# festBin.net
KiCad netlist of a schematic drawn in EAGLE
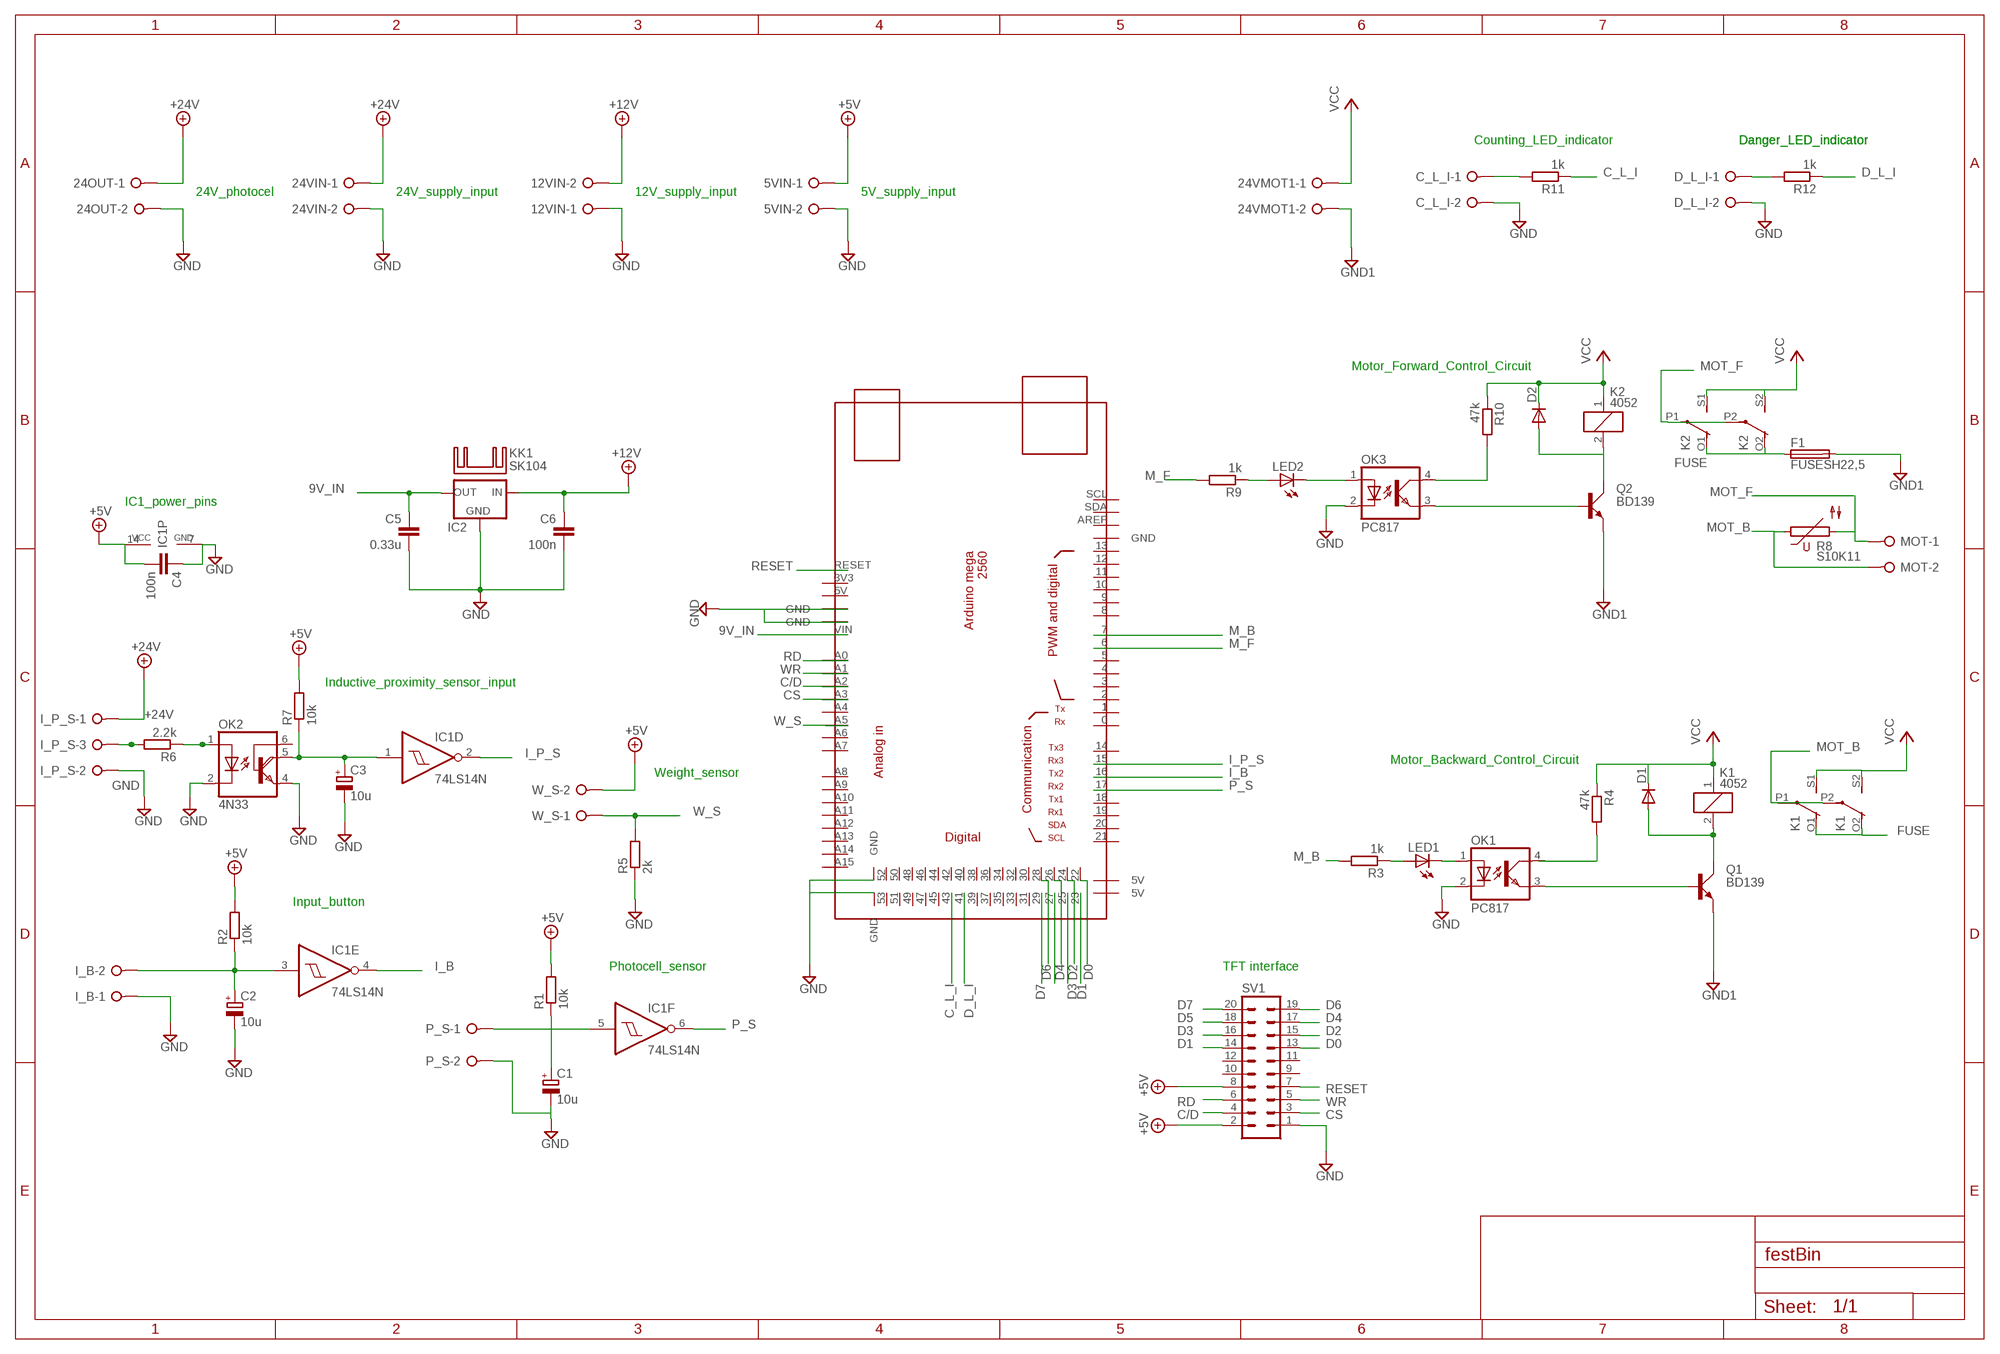
[diagram p0: schematic, sheet 1]

(export (version "E")
  (design (tool "Eeschema 10.0.6"))
  (components
    (comp (ref "5VIN")
      (value "W237-02P")
      (footprint "eagle-import:W237-132")
      (libsource (lib "eagle-import") (part "W237-02P"))
    )
    (comp (ref "12VIN")
      (value "W237-02P")
      (footprint "eagle-import:W237-132")
      (libsource (lib "eagle-import") (part "W237-02P"))
    )
    (comp (ref "24OUT")
      (value "W237-02P")
      (footprint "eagle-import:W237-132")
      (libsource (lib "eagle-import") (part "W237-02P"))
    )
    (comp (ref "24VIN")
      (value "W237-02P")
      (footprint "eagle-import:W237-132")
      (libsource (lib "eagle-import") (part "W237-02P"))
    )
    (comp (ref "24VMOT1")
      (value "W237-02P")
      (footprint "eagle-import:W237-132")
      (libsource (lib "eagle-import") (part "W237-02P"))
    )
    (comp (ref "C1")
      (value "10u")
      (footprint "eagle-import:E2,5-6")
      (libsource (lib "eagle-import") (part "CPOL-EUE2.5-6"))
    )
    (comp (ref "C2")
      (value "10u")
      (footprint "eagle-import:E2,5-6")
      (libsource (lib "eagle-import") (part "CPOL-EUE2.5-6"))
    )
    (comp (ref "C3")
      (value "10u")
      (footprint "eagle-import:E2,5-6")
      (libsource (lib "eagle-import") (part "CPOL-EUE2.5-6"))
    )
    (comp (ref "C4")
      (value "100n")
      (footprint "eagle-import:C050-024X044")
      (libsource (lib "eagle-import") (part "C-EU050-024X044"))
    )
    (comp (ref "C5")
      (value "0.33u")
      (footprint "eagle-import:C050-024X044")
      (libsource (lib "eagle-import") (part "C-EU050-024X044"))
    )
    (comp (ref "C6")
      (value "100n")
      (footprint "eagle-import:C050-024X044")
      (libsource (lib "eagle-import") (part "C-EU050-024X044"))
    )
    (comp (ref "C_L_I")
      (value "W237-02P")
      (footprint "eagle-import:W237-132")
      (libsource (lib "eagle-import") (part "W237-02P"))
    )
    (comp (ref "D1")
      (value "DIODE-DO41-10")
      (footprint "eagle-import:DO41-10")
      (libsource (lib "eagle-import") (part "DIODE-DO41-10"))
    )
    (comp (ref "D2")
      (value "DIODE-DO41-10")
      (footprint "eagle-import:DO41-10")
      (libsource (lib "eagle-import") (part "DIODE-DO41-10"))
    )
    (comp (ref "D_L_I")
      (value "W237-02P")
      (footprint "eagle-import:W237-132")
      (fields (field (name "OC_FARNELL") "unknown") (field (name "OC_NEWARK") "unknown"))
      (libsource (lib "eagle-import") (part "W237-02P"))
    )
    (comp (ref "F1")
      (value "FUSESH22,5")
      (footprint "eagle-import:SH22,5")
      (libsource (lib "eagle-import") (part "FUSESH22,5"))
    )
    (comp (ref "IC1")
      (value "74LS14N")
      (footprint "eagle-import:DIL14")
      (libsource (lib "eagle-import") (part "7414NLS"))
    )
    (comp (ref "IC2")
      (value "78XXS")
      (footprint "eagle-import:78XXS")
      (libsource (lib "eagle-import") (part "78XXS"))
    )
    (comp (ref "I_B")
      (value "W237-02P")
      (footprint "eagle-import:W237-132")
      (libsource (lib "eagle-import") (part "W237-02P"))
    )
    (comp (ref "I_P_S")
      (value "W237-3E")
      (footprint "eagle-import:W237-3E")
      (libsource (lib "eagle-import") (part "W237-3E"))
    )
    (comp (ref "K1")
      (value "4052")
      (footprint "eagle-import:F4052")
      (libsource (lib "eagle-import") (part "4052"))
    )
    (comp (ref "K2")
      (value "4052")
      (footprint "eagle-import:F4052")
      (libsource (lib "eagle-import") (part "4052"))
    )
    (comp (ref "KK1")
      (value "SK104")
      (footprint "eagle-import:SK104")
      (libsource (lib "eagle-import") (part "SK104"))
    )
    (comp (ref "LED1")
      (value "LED3MM")
      (footprint "eagle-import:LED3MM")
      (libsource (lib "eagle-import") (part "LED3MM"))
    )
    (comp (ref "LED2")
      (value "LED3MM")
      (footprint "eagle-import:LED3MM")
      (libsource (lib "eagle-import") (part "LED3MM"))
    )
    (comp (ref "MOT")
      (value "W237-02P")
      (footprint "eagle-import:W237-132")
      (fields (field (name "OC_FARNELL") "unknown") (field (name "OC_NEWARK") "unknown"))
      (libsource (lib "eagle-import") (part "W237-02P"))
    )
    (comp (ref "OK1")
      (value "PC817")
      (footprint "eagle-import:DIL04")
      (fields (field (name "MPN") "PC817X4J000F"))
      (libsource (lib "eagle-import") (part "PC817"))
    )
    (comp (ref "OK2")
      (value "4N33")
      (footprint "eagle-import:DIL06")
      (fields (field (name "MF") "VISHAY/TELEFUNKEN"))
      (libsource (lib "eagle-import") (part "4N33"))
    )
    (comp (ref "OK3")
      (value "PC817")
      (footprint "eagle-import:DIL04")
      (fields (field (name "MPN") "PC817X4J000F"))
      (libsource (lib "eagle-import") (part "PC817"))
    )
    (comp (ref "P_S")
      (value "W237-02P")
      (footprint "eagle-import:W237-132")
      (libsource (lib "eagle-import") (part "W237-02P"))
    )
    (comp (ref "Q1")
      (value "BD139")
      (footprint "eagle-import:TO126AV")
      (libsource (lib "eagle-import") (part "BD139"))
    )
    (comp (ref "Q2")
      (value "BD139")
      (footprint "eagle-import:TO126AV")
      (libsource (lib "eagle-import") (part "BD139"))
    )
    (comp (ref "R1")
      (value "10k")
      (footprint "eagle-import:0207_10")
      (libsource (lib "eagle-import") (part "R-EU_0207/10"))
    )
    (comp (ref "R2")
      (value "10k")
      (footprint "eagle-import:0207_10")
      (libsource (lib "eagle-import") (part "R-EU_0207/10"))
    )
    (comp (ref "R3")
      (value "1k")
      (footprint "eagle-import:0207_10")
      (libsource (lib "eagle-import") (part "R-EU_0207/10"))
    )
    (comp (ref "R4")
      (value "47k")
      (footprint "eagle-import:0207_10")
      (libsource (lib "eagle-import") (part "R-EU_0207/10"))
    )
    (comp (ref "R5")
      (value "2k")
      (footprint "eagle-import:0207_10")
      (libsource (lib "eagle-import") (part "R-EU_0207/10"))
    )
    (comp (ref "R6")
      (value "2.2k")
      (footprint "eagle-import:0207_10")
      (libsource (lib "eagle-import") (part "R-EU_0207/10"))
    )
    (comp (ref "R7")
      (value "10k")
      (footprint "eagle-import:0207_10")
      (libsource (lib "eagle-import") (part "R-EU_0207/10"))
    )
    (comp (ref "R8")
      (value "S10K11")
      (footprint "eagle-import:S10K11")
      (libsource (lib "eagle-import") (part "S10K11"))
    )
    (comp (ref "R9")
      (value "1k")
      (footprint "eagle-import:0207_10")
      (libsource (lib "eagle-import") (part "R-EU_0207/10"))
    )
    (comp (ref "R10")
      (value "47k")
      (footprint "eagle-import:0207_10")
      (libsource (lib "eagle-import") (part "R-EU_0207/10"))
    )
    (comp (ref "R11")
      (value "1k")
      (footprint "eagle-import:0207_10")
      (libsource (lib "eagle-import") (part "R-EU_0207/10"))
    )
    (comp (ref "R12")
      (value "1k")
      (footprint "eagle-import:0207_10")
      (libsource (lib "eagle-import") (part "R-EU_0207/10"))
    )
    (comp (ref "SV1")
      (value "ML20")
      (footprint "eagle-import:ML20")
      (libsource (lib "eagle-import") (part "ML20"))
    )
    (comp (ref "U$1")
      (value "MEGA_DEVICE")
      (footprint "eagle-import:MEGABOX")
      (libsource (lib "eagle-import") (part "MEGA_DEVICE"))
    )
    (comp (ref "W_S")
      (value "W237-02P")
      (footprint "eagle-import:W237-132")
      (libsource (lib "eagle-import") (part "W237-02P"))
    )
  )
  (nets
    (net (code "1") (name "+5V") (class "Default")
      (node (ref "5VIN") (pin "1") (pinfunction "KL_1") (pintype "passive"))
      (node (ref "C4") (pin "2") (pinfunction "2_2") (pintype "passive"))
      (node (ref "IC1") (pin "14") (pinfunction "VCC_14") (pintype "power_in"))
      (node (ref "R1") (pin "2") (pinfunction "2_2") (pintype "passive"))
      (node (ref "R2") (pin "2") (pinfunction "2_2") (pintype "passive"))
      (node (ref "R7") (pin "2") (pinfunction "2_2") (pintype "passive"))
      (node (ref "SV1") (pin "2") (pinfunction "2_2") (pintype "passive"))
      (node (ref "SV1") (pin "8") (pinfunction "8_8") (pintype "passive"))
      (node (ref "W_S") (pin "2") (pinfunction "KL_2") (pintype "passive"))
    )
    (net (code "2") (name "+12V") (class "Default")
      (node (ref "12VIN") (pin "2") (pinfunction "KL_2") (pintype "passive"))
      (node (ref "C6") (pin "1") (pinfunction "1_1") (pintype "passive"))
      (node (ref "IC2") (pin "IN") (pinfunction "IN_IN") (pintype "input"))
    )
    (net (code "3") (name "+24V") (class "Default")
      (node (ref "24OUT") (pin "1") (pinfunction "KL_1") (pintype "passive"))
      (node (ref "24VIN") (pin "1") (pinfunction "KL_1") (pintype "passive"))
      (node (ref "I_P_S") (pin "1") (pinfunction "KL_1") (pintype "passive"))
    )
    (net (code "4") (name "/9V_IN") (class "Default")
      (node (ref "C5") (pin "1") (pinfunction "1_1") (pintype "passive"))
      (node (ref "IC2") (pin "OUT") (pinfunction "OUT_OUT") (pintype "passive"))
      (node (ref "U$1") (pin "VIN") (pinfunction "VIN_VIN") (pintype "bidirectional"))
    )
    (net (code "5") (name "/CS") (class "Default")
      (node (ref "SV1") (pin "3") (pinfunction "3_3") (pintype "passive"))
      (node (ref "U$1") (pin "A3") (pinfunction "A3_A3") (pintype "bidirectional"))
    )
    (net (code "6") (name "/C_L_I") (class "Default")
      (node (ref "R11") (pin "1") (pinfunction "1_1") (pintype "passive"))
      (node (ref "U$1") (pin "43") (pinfunction "43_43") (pintype "bidirectional"))
    )
    (net (code "7") (name "/C{slash}D") (class "Default")
      (node (ref "SV1") (pin "4") (pinfunction "4_4") (pintype "passive"))
      (node (ref "U$1") (pin "A2") (pinfunction "A2_A2") (pintype "bidirectional"))
    )
    (net (code "8") (name "/D0") (class "Default")
      (node (ref "SV1") (pin "13") (pinfunction "13_13") (pintype "passive"))
      (node (ref "U$1") (pin "22") (pinfunction "22_22") (pintype "bidirectional"))
    )
    (net (code "9") (name "/D1") (class "Default")
      (node (ref "SV1") (pin "14") (pinfunction "14_14") (pintype "passive"))
      (node (ref "U$1") (pin "23") (pinfunction "23_23") (pintype "bidirectional"))
    )
    (net (code "10") (name "/D2") (class "Default")
      (node (ref "SV1") (pin "15") (pinfunction "15_15") (pintype "passive"))
      (node (ref "U$1") (pin "24") (pinfunction "24_24") (pintype "bidirectional"))
    )
    (net (code "11") (name "/D3") (class "Default")
      (node (ref "SV1") (pin "16") (pinfunction "16_16") (pintype "passive"))
      (node (ref "U$1") (pin "25") (pinfunction "25_25") (pintype "bidirectional"))
    )
    (net (code "12") (name "/D4") (class "Default")
      (node (ref "SV1") (pin "17") (pinfunction "17_17") (pintype "passive"))
      (node (ref "U$1") (pin "26") (pinfunction "26_26") (pintype "bidirectional"))
    )
    (net (code "13") (name "/D5") (class "Default")
      (node (ref "SV1") (pin "18") (pinfunction "18_18") (pintype "passive"))
      (node (ref "U$1") (pin "27") (pinfunction "27_27") (pintype "bidirectional"))
    )
    (net (code "14") (name "/D6") (class "Default")
      (node (ref "SV1") (pin "19") (pinfunction "19_19") (pintype "passive"))
      (node (ref "U$1") (pin "28") (pinfunction "28_28") (pintype "bidirectional"))
    )
    (net (code "15") (name "/D7") (class "Default")
      (node (ref "SV1") (pin "20") (pinfunction "20_20") (pintype "passive"))
      (node (ref "U$1") (pin "29") (pinfunction "29_29") (pintype "bidirectional"))
    )
    (net (code "16") (name "/D_L_I") (class "Default")
      (node (ref "R12") (pin "1") (pinfunction "1_1") (pintype "passive"))
      (node (ref "U$1") (pin "41") (pinfunction "41_41") (pintype "bidirectional"))
    )
    (net (code "17") (name "/FUSE") (class "Default")
      (node (ref "F1") (pin "1") (pinfunction "1_1") (pintype "passive"))
      (node (ref "K1") (pin "O1") (pinfunction "O_O1") (pintype "passive"))
      (node (ref "K1") (pin "O2") (pinfunction "O_O2") (pintype "passive"))
      (node (ref "K2") (pin "O1") (pinfunction "O_O1") (pintype "passive"))
      (node (ref "K2") (pin "O2") (pinfunction "O_O2") (pintype "passive"))
    )
    (net (code "18") (name "/I_B") (class "Default")
      (node (ref "IC1") (pin "4") (pinfunction "O_4") (pintype "output"))
      (node (ref "U$1") (pin "16") (pinfunction "16_16") (pintype "bidirectional"))
    )
    (net (code "19") (name "/I_P_S") (class "Default")
      (node (ref "IC1") (pin "2") (pinfunction "O_2") (pintype "output"))
      (node (ref "U$1") (pin "15") (pinfunction "15_15") (pintype "bidirectional"))
    )
    (net (code "20") (name "/MOT_B") (class "Default")
      (node (ref "K1") (pin "P1") (pinfunction "P_P1") (pintype "passive"))
      (node (ref "K1") (pin "P2") (pinfunction "P_P2") (pintype "passive"))
      (node (ref "MOT") (pin "2") (pinfunction "KL_2") (pintype "passive"))
      (node (ref "R8") (pin "1") (pinfunction "1_1") (pintype "passive"))
    )
    (net (code "21") (name "/MOT_F") (class "Default")
      (node (ref "K2") (pin "P1") (pinfunction "P_P1") (pintype "passive"))
      (node (ref "K2") (pin "P2") (pinfunction "P_P2") (pintype "passive"))
      (node (ref "MOT") (pin "1") (pinfunction "KL_1") (pintype "passive"))
      (node (ref "R8") (pin "2") (pinfunction "2_2") (pintype "passive"))
    )
    (net (code "22") (name "/M_B") (class "Default")
      (node (ref "R3") (pin "2") (pinfunction "2_2") (pintype "passive"))
      (node (ref "U$1") (pin "7") (pinfunction "7_7") (pintype "bidirectional"))
    )
    (net (code "23") (name "/M_F") (class "Default")
      (node (ref "R9") (pin "2") (pinfunction "2_2") (pintype "passive"))
      (node (ref "U$1") (pin "6") (pinfunction "6_6") (pintype "bidirectional"))
    )
    (net (code "24") (name "/P_S") (class "Default")
      (node (ref "IC1") (pin "6") (pinfunction "O_6") (pintype "output"))
      (node (ref "U$1") (pin "17") (pinfunction "17_17") (pintype "bidirectional"))
    )
    (net (code "25") (name "/RD") (class "Default")
      (node (ref "SV1") (pin "6") (pinfunction "6_6") (pintype "passive"))
      (node (ref "U$1") (pin "A0") (pinfunction "A0_A0") (pintype "bidirectional"))
    )
    (net (code "26") (name "/RESET") (class "Default")
      (node (ref "SV1") (pin "7") (pinfunction "7_7") (pintype "passive"))
      (node (ref "U$1") (pin "RESET") (pinfunction "RESET_RESET") (pintype "bidirectional"))
    )
    (net (code "27") (name "/WR") (class "Default")
      (node (ref "SV1") (pin "5") (pinfunction "5_5") (pintype "passive"))
      (node (ref "U$1") (pin "A1") (pinfunction "A1_A1") (pintype "bidirectional"))
    )
    (net (code "28") (name "/W_S") (class "Default")
      (node (ref "R5") (pin "2") (pinfunction "2_2") (pintype "passive"))
      (node (ref "U$1") (pin "A5") (pinfunction "A5_A5") (pintype "bidirectional"))
      (node (ref "W_S") (pin "1") (pinfunction "KL_1") (pintype "passive"))
    )
    (net (code "29") (name "GND") (class "Default")
      (node (ref "12VIN") (pin "1") (pinfunction "KL_1") (pintype "passive"))
      (node (ref "24OUT") (pin "2") (pinfunction "KL_2") (pintype "passive"))
      (node (ref "24VIN") (pin "2") (pinfunction "KL_2") (pintype "passive"))
      (node (ref "5VIN") (pin "2") (pinfunction "KL_2") (pintype "passive"))
      (node (ref "C1") (pin "-") (pinfunction "-_-") (pintype "passive"))
      (node (ref "C2") (pin "-") (pinfunction "-_-") (pintype "passive"))
      (node (ref "C3") (pin "-") (pinfunction "-_-") (pintype "passive"))
      (node (ref "C4") (pin "1") (pinfunction "1_1") (pintype "passive"))
      (node (ref "C5") (pin "2") (pinfunction "2_2") (pintype "passive"))
      (node (ref "C6") (pin "2") (pinfunction "2_2") (pintype "passive"))
      (node (ref "C_L_I") (pin "2") (pinfunction "KL_2") (pintype "passive"))
      (node (ref "D_L_I") (pin "2") (pinfunction "KL_2") (pintype "passive"))
      (node (ref "IC1") (pin "7") (pinfunction "GND_7") (pintype "power_in"))
      (node (ref "IC2") (pin "GND") (pinfunction "GND_GND") (pintype "input"))
      (node (ref "I_B") (pin "1") (pinfunction "KL_1") (pintype "passive"))
      (node (ref "I_P_S") (pin "2") (pinfunction "KL_2") (pintype "passive"))
      (node (ref "OK1") (pin "2") (pinfunction "C_2") (pintype "passive"))
      (node (ref "OK2") (pin "2") (pinfunction "C_2") (pintype "passive"))
      (node (ref "OK2") (pin "4") (pinfunction "E_4") (pintype "passive"))
      (node (ref "OK3") (pin "2") (pinfunction "C_2") (pintype "passive"))
      (node (ref "P_S") (pin "2") (pinfunction "KL_2") (pintype "passive"))
      (node (ref "R5") (pin "1") (pinfunction "1_1") (pintype "passive"))
      (node (ref "SV1") (pin "1") (pinfunction "1_1") (pintype "passive"))
      (node (ref "U$1") (pin "GND@2") (pinfunction "GND_GND@2") (pintype "bidirectional"))
      (node (ref "U$1") (pin "GND@3") (pinfunction "GND_GND@3") (pintype "bidirectional"))
      (node (ref "U$1") (pin "GND@6") (pinfunction "GND_GND@6") (pintype "bidirectional"))
      (node (ref "U$1") (pin "GND@7") (pinfunction "GND_GND@7") (pintype "bidirectional"))
    )
    (net (code "30") (name "GND1") (class "Default")
      (node (ref "24VMOT1") (pin "2") (pinfunction "KL_2") (pintype "passive"))
      (node (ref "F1") (pin "2") (pinfunction "2_2") (pintype "passive"))
      (node (ref "Q1") (pin "E") (pinfunction "E_E") (pintype "passive"))
      (node (ref "Q2") (pin "E") (pinfunction "E_E") (pintype "passive"))
    )
    (net (code "31") (name "Net-(C_L_IA-KL)") (class "Default")
      (node (ref "C_L_I") (pin "1") (pinfunction "KL_1") (pintype "passive"))
      (node (ref "R11") (pin "2") (pinfunction "2_2") (pintype "passive"))
    )
    (net (code "32") (name "Net-(D1-PadA)") (class "Default")
      (node (ref "D1") (pin "A") (pinfunction "A_A") (pintype "passive"))
      (node (ref "K1") (pin "2") (pinfunction "2_2") (pintype "passive"))
      (node (ref "Q1") (pin "C") (pinfunction "C_C") (pintype "passive"))
    )
    (net (code "33") (name "Net-(D2-PadA)") (class "Default")
      (node (ref "D2") (pin "A") (pinfunction "A_A") (pintype "passive"))
      (node (ref "K2") (pin "2") (pinfunction "2_2") (pintype "passive"))
      (node (ref "Q2") (pin "C") (pinfunction "C_C") (pintype "passive"))
    )
    (net (code "34") (name "Net-(D_L_IA-KL)") (class "Default")
      (node (ref "D_L_I") (pin "1") (pinfunction "KL_1") (pintype "passive"))
      (node (ref "R12") (pin "2") (pinfunction "2_2") (pintype "passive"))
    )
    (net (code "35") (name "Net-(IC1D-I)") (class "Default")
      (node (ref "C3") (pin "+") (pinfunction "+_+") (pintype "passive"))
      (node (ref "IC1") (pin "1") (pinfunction "I_1") (pintype "input"))
      (node (ref "OK2") (pin "5") (pinfunction "COL_5") (pintype "passive"))
      (node (ref "R7") (pin "1") (pinfunction "1_1") (pintype "passive"))
    )
    (net (code "36") (name "Net-(IC1E-I)") (class "Default")
      (node (ref "C2") (pin "+") (pinfunction "+_+") (pintype "passive"))
      (node (ref "IC1") (pin "3") (pinfunction "I_3") (pintype "input"))
      (node (ref "I_B") (pin "2") (pinfunction "KL_2") (pintype "passive"))
      (node (ref "R2") (pin "1") (pinfunction "1_1") (pintype "passive"))
    )
    (net (code "37") (name "Net-(IC1F-I)") (class "Default")
      (node (ref "C1") (pin "+") (pinfunction "+_+") (pintype "passive"))
      (node (ref "IC1") (pin "5") (pinfunction "I_5") (pintype "input"))
      (node (ref "P_S") (pin "1") (pinfunction "KL_1") (pintype "passive"))
      (node (ref "R1") (pin "1") (pinfunction "1_1") (pintype "passive"))
    )
    (net (code "38") (name "Net-(I_P_SC-KL)") (class "Default")
      (node (ref "I_P_S") (pin "3") (pinfunction "KL_3") (pintype "passive"))
      (node (ref "R6") (pin "2") (pinfunction "2_2") (pintype "passive"))
    )
    (net (code "39") (name "Net-(LED1-C)") (class "Default")
      (node (ref "LED1") (pin "K") (pinfunction "C_K") (pintype "passive"))
      (node (ref "OK1") (pin "1") (pinfunction "A_1") (pintype "passive"))
    )
    (net (code "40") (name "Net-(LED1-PadA)") (class "Default")
      (node (ref "LED1") (pin "A") (pinfunction "A_A") (pintype "passive"))
      (node (ref "R3") (pin "1") (pinfunction "1_1") (pintype "passive"))
    )
    (net (code "41") (name "Net-(LED2-C)") (class "Default")
      (node (ref "LED2") (pin "K") (pinfunction "C_K") (pintype "passive"))
      (node (ref "OK3") (pin "1") (pinfunction "A_1") (pintype "passive"))
    )
    (net (code "42") (name "Net-(LED2-PadA)") (class "Default")
      (node (ref "LED2") (pin "A") (pinfunction "A_A") (pintype "passive"))
      (node (ref "R9") (pin "1") (pinfunction "1_1") (pintype "passive"))
    )
    (net (code "43") (name "Net-(OK1-COL)") (class "Default")
      (node (ref "OK1") (pin "4") (pinfunction "COL_4") (pintype "passive"))
      (node (ref "R4") (pin "2") (pinfunction "2_2") (pintype "passive"))
    )
    (net (code "44") (name "Net-(OK1-EMIT)") (class "Default")
      (node (ref "OK1") (pin "3") (pinfunction "EMIT_3") (pintype "passive"))
      (node (ref "Q1") (pin "B") (pinfunction "B_B") (pintype "passive"))
    )
    (net (code "45") (name "Net-(OK2-A)") (class "Default")
      (node (ref "OK2") (pin "1") (pinfunction "A_1") (pintype "passive"))
      (node (ref "R6") (pin "1") (pinfunction "1_1") (pintype "passive"))
    )
    (net (code "46") (name "Net-(OK3-COL)") (class "Default")
      (node (ref "OK3") (pin "4") (pinfunction "COL_4") (pintype "passive"))
      (node (ref "R10") (pin "2") (pinfunction "2_2") (pintype "passive"))
    )
    (net (code "47") (name "Net-(OK3-EMIT)") (class "Default")
      (node (ref "OK3") (pin "3") (pinfunction "EMIT_3") (pintype "passive"))
      (node (ref "Q2") (pin "B") (pinfunction "B_B") (pintype "passive"))
    )
    (net (code "48") (name "VCC") (class "Default")
      (node (ref "24VMOT1") (pin "1") (pinfunction "KL_1") (pintype "passive"))
      (node (ref "D1") (pin "C") (pinfunction "C_C") (pintype "passive"))
      (node (ref "D2") (pin "C") (pinfunction "C_C") (pintype "passive"))
      (node (ref "K1") (pin "1") (pinfunction "1_1") (pintype "passive"))
      (node (ref "K1") (pin "S1") (pinfunction "S_S1") (pintype "passive"))
      (node (ref "K1") (pin "S2") (pinfunction "S_S2") (pintype "passive"))
      (node (ref "K2") (pin "1") (pinfunction "1_1") (pintype "passive"))
      (node (ref "K2") (pin "S1") (pinfunction "S_S1") (pintype "passive"))
      (node (ref "K2") (pin "S2") (pinfunction "S_S2") (pintype "passive"))
      (node (ref "R10") (pin "1") (pinfunction "1_1") (pintype "passive"))
      (node (ref "R4") (pin "1") (pinfunction "1_1") (pintype "passive"))
    )
    (net (code "49") (name "unconnected-(OK2-B-Pad6)") (class "Default")
      (node (ref "OK2") (pin "6") (pinfunction "B_6") (pintype "passive"))
    )
    (net (code "50") (name "unconnected-(SV1-Pad9)") (class "Default")
      (node (ref "SV1") (pin "9") (pinfunction "9_9") (pintype "passive"))
    )
    (net (code "51") (name "unconnected-(SV1-Pad10)") (class "Default")
      (node (ref "SV1") (pin "10") (pinfunction "10_10") (pintype "passive"))
    )
    (net (code "52") (name "unconnected-(SV1-Pad11)") (class "Default")
      (node (ref "SV1") (pin "11") (pinfunction "11_11") (pintype "passive"))
    )
    (net (code "53") (name "unconnected-(SV1-Pad12)") (class "Default")
      (node (ref "SV1") (pin "12") (pinfunction "12_12") (pintype "passive"))
    )
    (net (code "54") (name "unconnected-(U$1-5V-PadGND@4)") (class "Default")
      (node (ref "U$1") (pin "GND@4") (pinfunction "5V_GND@4") (pintype "bidirectional"))
    )
    (net (code "55") (name "unconnected-(U$1-5V-PadGND@5)") (class "Default")
      (node (ref "U$1") (pin "GND@5") (pinfunction "5V_GND@5") (pintype "bidirectional"))
    )
    (net (code "56") (name "unconnected-(U$1-GND-PadGND@1)") (class "Default")
      (node (ref "U$1") (pin "GND@1") (pinfunction "GND_GND@1") (pintype "bidirectional"))
    )
    (net (code "57") (name "unconnected-(U$1-Pad0)") (class "Default")
      (node (ref "U$1") (pin "0") (pinfunction "0_0") (pintype "bidirectional"))
    )
    (net (code "58") (name "unconnected-(U$1-Pad1)") (class "Default")
      (node (ref "U$1") (pin "1") (pinfunction "1_1") (pintype "bidirectional"))
    )
    (net (code "59") (name "unconnected-(U$1-Pad2)") (class "Default")
      (node (ref "U$1") (pin "2") (pinfunction "2_2") (pintype "bidirectional"))
    )
    (net (code "60") (name "unconnected-(U$1-Pad3)") (class "Default")
      (node (ref "U$1") (pin "3") (pinfunction "3_3") (pintype "bidirectional"))
    )
    (net (code "61") (name "unconnected-(U$1-Pad3V3)") (class "Default")
      (node (ref "U$1") (pin "3V3") (pinfunction "3V3_3V3") (pintype "bidirectional"))
    )
    (net (code "62") (name "unconnected-(U$1-Pad4)") (class "Default")
      (node (ref "U$1") (pin "4") (pinfunction "4_4") (pintype "bidirectional"))
    )
    (net (code "63") (name "unconnected-(U$1-Pad5)") (class "Default")
      (node (ref "U$1") (pin "5") (pinfunction "5_5") (pintype "bidirectional"))
    )
    (net (code "64") (name "unconnected-(U$1-Pad5V)") (class "Default")
      (node (ref "U$1") (pin "5V") (pinfunction "5V_5V") (pintype "bidirectional"))
    )
    (net (code "65") (name "unconnected-(U$1-Pad8)") (class "Default")
      (node (ref "U$1") (pin "8") (pinfunction "8_8") (pintype "bidirectional"))
    )
    (net (code "66") (name "unconnected-(U$1-Pad9)") (class "Default")
      (node (ref "U$1") (pin "9") (pinfunction "9_9") (pintype "bidirectional"))
    )
    (net (code "67") (name "unconnected-(U$1-Pad10)") (class "Default")
      (node (ref "U$1") (pin "10") (pinfunction "10_10") (pintype "bidirectional"))
    )
    (net (code "68") (name "unconnected-(U$1-Pad11)") (class "Default")
      (node (ref "U$1") (pin "11") (pinfunction "11_11") (pintype "bidirectional"))
    )
    (net (code "69") (name "unconnected-(U$1-Pad12)") (class "Default")
      (node (ref "U$1") (pin "12") (pinfunction "12_12") (pintype "bidirectional"))
    )
    (net (code "70") (name "unconnected-(U$1-Pad13)") (class "Default")
      (node (ref "U$1") (pin "13") (pinfunction "13_13") (pintype "bidirectional"))
    )
    (net (code "71") (name "unconnected-(U$1-Pad14)") (class "Default")
      (node (ref "U$1") (pin "14") (pinfunction "14_14") (pintype "bidirectional"))
    )
    (net (code "72") (name "unconnected-(U$1-Pad18)") (class "Default")
      (node (ref "U$1") (pin "18") (pinfunction "18_18") (pintype "bidirectional"))
    )
    (net (code "73") (name "unconnected-(U$1-Pad19)") (class "Default")
      (node (ref "U$1") (pin "19") (pinfunction "19_19") (pintype "bidirectional"))
    )
    (net (code "74") (name "unconnected-(U$1-Pad20)") (class "Default")
      (node (ref "U$1") (pin "20") (pinfunction "20_20") (pintype "bidirectional"))
    )
    (net (code "75") (name "unconnected-(U$1-Pad21)") (class "Default")
      (node (ref "U$1") (pin "21") (pinfunction "21_21") (pintype "bidirectional"))
    )
    (net (code "76") (name "unconnected-(U$1-Pad30)") (class "Default")
      (node (ref "U$1") (pin "30") (pinfunction "30_30") (pintype "bidirectional"))
    )
    (net (code "77") (name "unconnected-(U$1-Pad31)") (class "Default")
      (node (ref "U$1") (pin "31") (pinfunction "31_31") (pintype "bidirectional"))
    )
    (net (code "78") (name "unconnected-(U$1-Pad32)") (class "Default")
      (node (ref "U$1") (pin "32") (pinfunction "32_32") (pintype "bidirectional"))
    )
    (net (code "79") (name "unconnected-(U$1-Pad33)") (class "Default")
      (node (ref "U$1") (pin "33") (pinfunction "33_33") (pintype "bidirectional"))
    )
    (net (code "80") (name "unconnected-(U$1-Pad34)") (class "Default")
      (node (ref "U$1") (pin "34") (pinfunction "34_34") (pintype "bidirectional"))
    )
    (net (code "81") (name "unconnected-(U$1-Pad35)") (class "Default")
      (node (ref "U$1") (pin "35") (pinfunction "35_35") (pintype "bidirectional"))
    )
    (net (code "82") (name "unconnected-(U$1-Pad36)") (class "Default")
      (node (ref "U$1") (pin "36") (pinfunction "36_36") (pintype "bidirectional"))
    )
    (net (code "83") (name "unconnected-(U$1-Pad37)") (class "Default")
      (node (ref "U$1") (pin "37") (pinfunction "37_37") (pintype "bidirectional"))
    )
    (net (code "84") (name "unconnected-(U$1-Pad38)") (class "Default")
      (node (ref "U$1") (pin "38") (pinfunction "38_38") (pintype "bidirectional"))
    )
    (net (code "85") (name "unconnected-(U$1-Pad39)") (class "Default")
      (node (ref "U$1") (pin "39") (pinfunction "39_39") (pintype "bidirectional"))
    )
    (net (code "86") (name "unconnected-(U$1-Pad40)") (class "Default")
      (node (ref "U$1") (pin "40") (pinfunction "40_40") (pintype "bidirectional"))
    )
    (net (code "87") (name "unconnected-(U$1-Pad42)") (class "Default")
      (node (ref "U$1") (pin "42") (pinfunction "42_42") (pintype "bidirectional"))
    )
    (net (code "88") (name "unconnected-(U$1-Pad44)") (class "Default")
      (node (ref "U$1") (pin "44") (pinfunction "44_44") (pintype "bidirectional"))
    )
    (net (code "89") (name "unconnected-(U$1-Pad45)") (class "Default")
      (node (ref "U$1") (pin "45") (pinfunction "45_45") (pintype "bidirectional"))
    )
    (net (code "90") (name "unconnected-(U$1-Pad46)") (class "Default")
      (node (ref "U$1") (pin "46") (pinfunction "46_46") (pintype "bidirectional"))
    )
    (net (code "91") (name "unconnected-(U$1-Pad47)") (class "Default")
      (node (ref "U$1") (pin "47") (pinfunction "47_47") (pintype "bidirectional"))
    )
    (net (code "92") (name "unconnected-(U$1-Pad48)") (class "Default")
      (node (ref "U$1") (pin "48") (pinfunction "48_48") (pintype "bidirectional"))
    )
    (net (code "93") (name "unconnected-(U$1-Pad49)") (class "Default")
      (node (ref "U$1") (pin "49") (pinfunction "49_49") (pintype "bidirectional"))
    )
    (net (code "94") (name "unconnected-(U$1-Pad50)") (class "Default")
      (node (ref "U$1") (pin "50") (pinfunction "50_50") (pintype "bidirectional"))
    )
    (net (code "95") (name "unconnected-(U$1-Pad51)") (class "Default")
      (node (ref "U$1") (pin "51") (pinfunction "51_51") (pintype "bidirectional"))
    )
    (net (code "96") (name "unconnected-(U$1-Pad52)") (class "Default")
      (node (ref "U$1") (pin "52") (pinfunction "52_52") (pintype "bidirectional"))
    )
    (net (code "97") (name "unconnected-(U$1-Pad53)") (class "Default")
      (node (ref "U$1") (pin "53") (pinfunction "53_53") (pintype "bidirectional"))
    )
    (net (code "98") (name "unconnected-(U$1-PadA4)") (class "Default")
      (node (ref "U$1") (pin "A4") (pinfunction "A4_A4") (pintype "bidirectional"))
    )
    (net (code "99") (name "unconnected-(U$1-PadA6)") (class "Default")
      (node (ref "U$1") (pin "A6") (pinfunction "A6_A6") (pintype "bidirectional"))
    )
    (net (code "100") (name "unconnected-(U$1-PadA7)") (class "Default")
      (node (ref "U$1") (pin "A7") (pinfunction "A7_A7") (pintype "bidirectional"))
    )
    (net (code "101") (name "unconnected-(U$1-PadA8)") (class "Default")
      (node (ref "U$1") (pin "A8") (pinfunction "A8_A8") (pintype "bidirectional"))
    )
    (net (code "102") (name "unconnected-(U$1-PadA9)") (class "Default")
      (node (ref "U$1") (pin "A9") (pinfunction "A9_A9") (pintype "bidirectional"))
    )
    (net (code "103") (name "unconnected-(U$1-PadA10)") (class "Default")
      (node (ref "U$1") (pin "A10") (pinfunction "A10_A10") (pintype "bidirectional"))
    )
    (net (code "104") (name "unconnected-(U$1-PadA11)") (class "Default")
      (node (ref "U$1") (pin "A11") (pinfunction "A11_A11") (pintype "bidirectional"))
    )
    (net (code "105") (name "unconnected-(U$1-PadA12)") (class "Default")
      (node (ref "U$1") (pin "A12") (pinfunction "A12_A12") (pintype "bidirectional"))
    )
    (net (code "106") (name "unconnected-(U$1-PadA13)") (class "Default")
      (node (ref "U$1") (pin "A13") (pinfunction "A13_A13") (pintype "bidirectional"))
    )
    (net (code "107") (name "unconnected-(U$1-PadA14)") (class "Default")
      (node (ref "U$1") (pin "A14") (pinfunction "A14_A14") (pintype "bidirectional"))
    )
    (net (code "108") (name "unconnected-(U$1-PadA15)") (class "Default")
      (node (ref "U$1") (pin "A15") (pinfunction "A15_A15") (pintype "bidirectional"))
    )
    (net (code "109") (name "unconnected-(U$1-PadAREF)") (class "Default")
      (node (ref "U$1") (pin "AREF") (pinfunction "AREF_AREF") (pintype "bidirectional"))
    )
    (net (code "110") (name "unconnected-(U$1-PadSCL)") (class "Default")
      (node (ref "U$1") (pin "SCL") (pinfunction "SCL_SCL") (pintype "bidirectional"))
    )
    (net (code "111") (name "unconnected-(U$1-PadSDA)") (class "Default")
      (node (ref "U$1") (pin "SDA") (pinfunction "SDA_SDA") (pintype "bidirectional"))
    )
  )
)
